# SCH_Esquematico_pastillero.net
KiCad netlist of a schematic drawn in EasyEDA
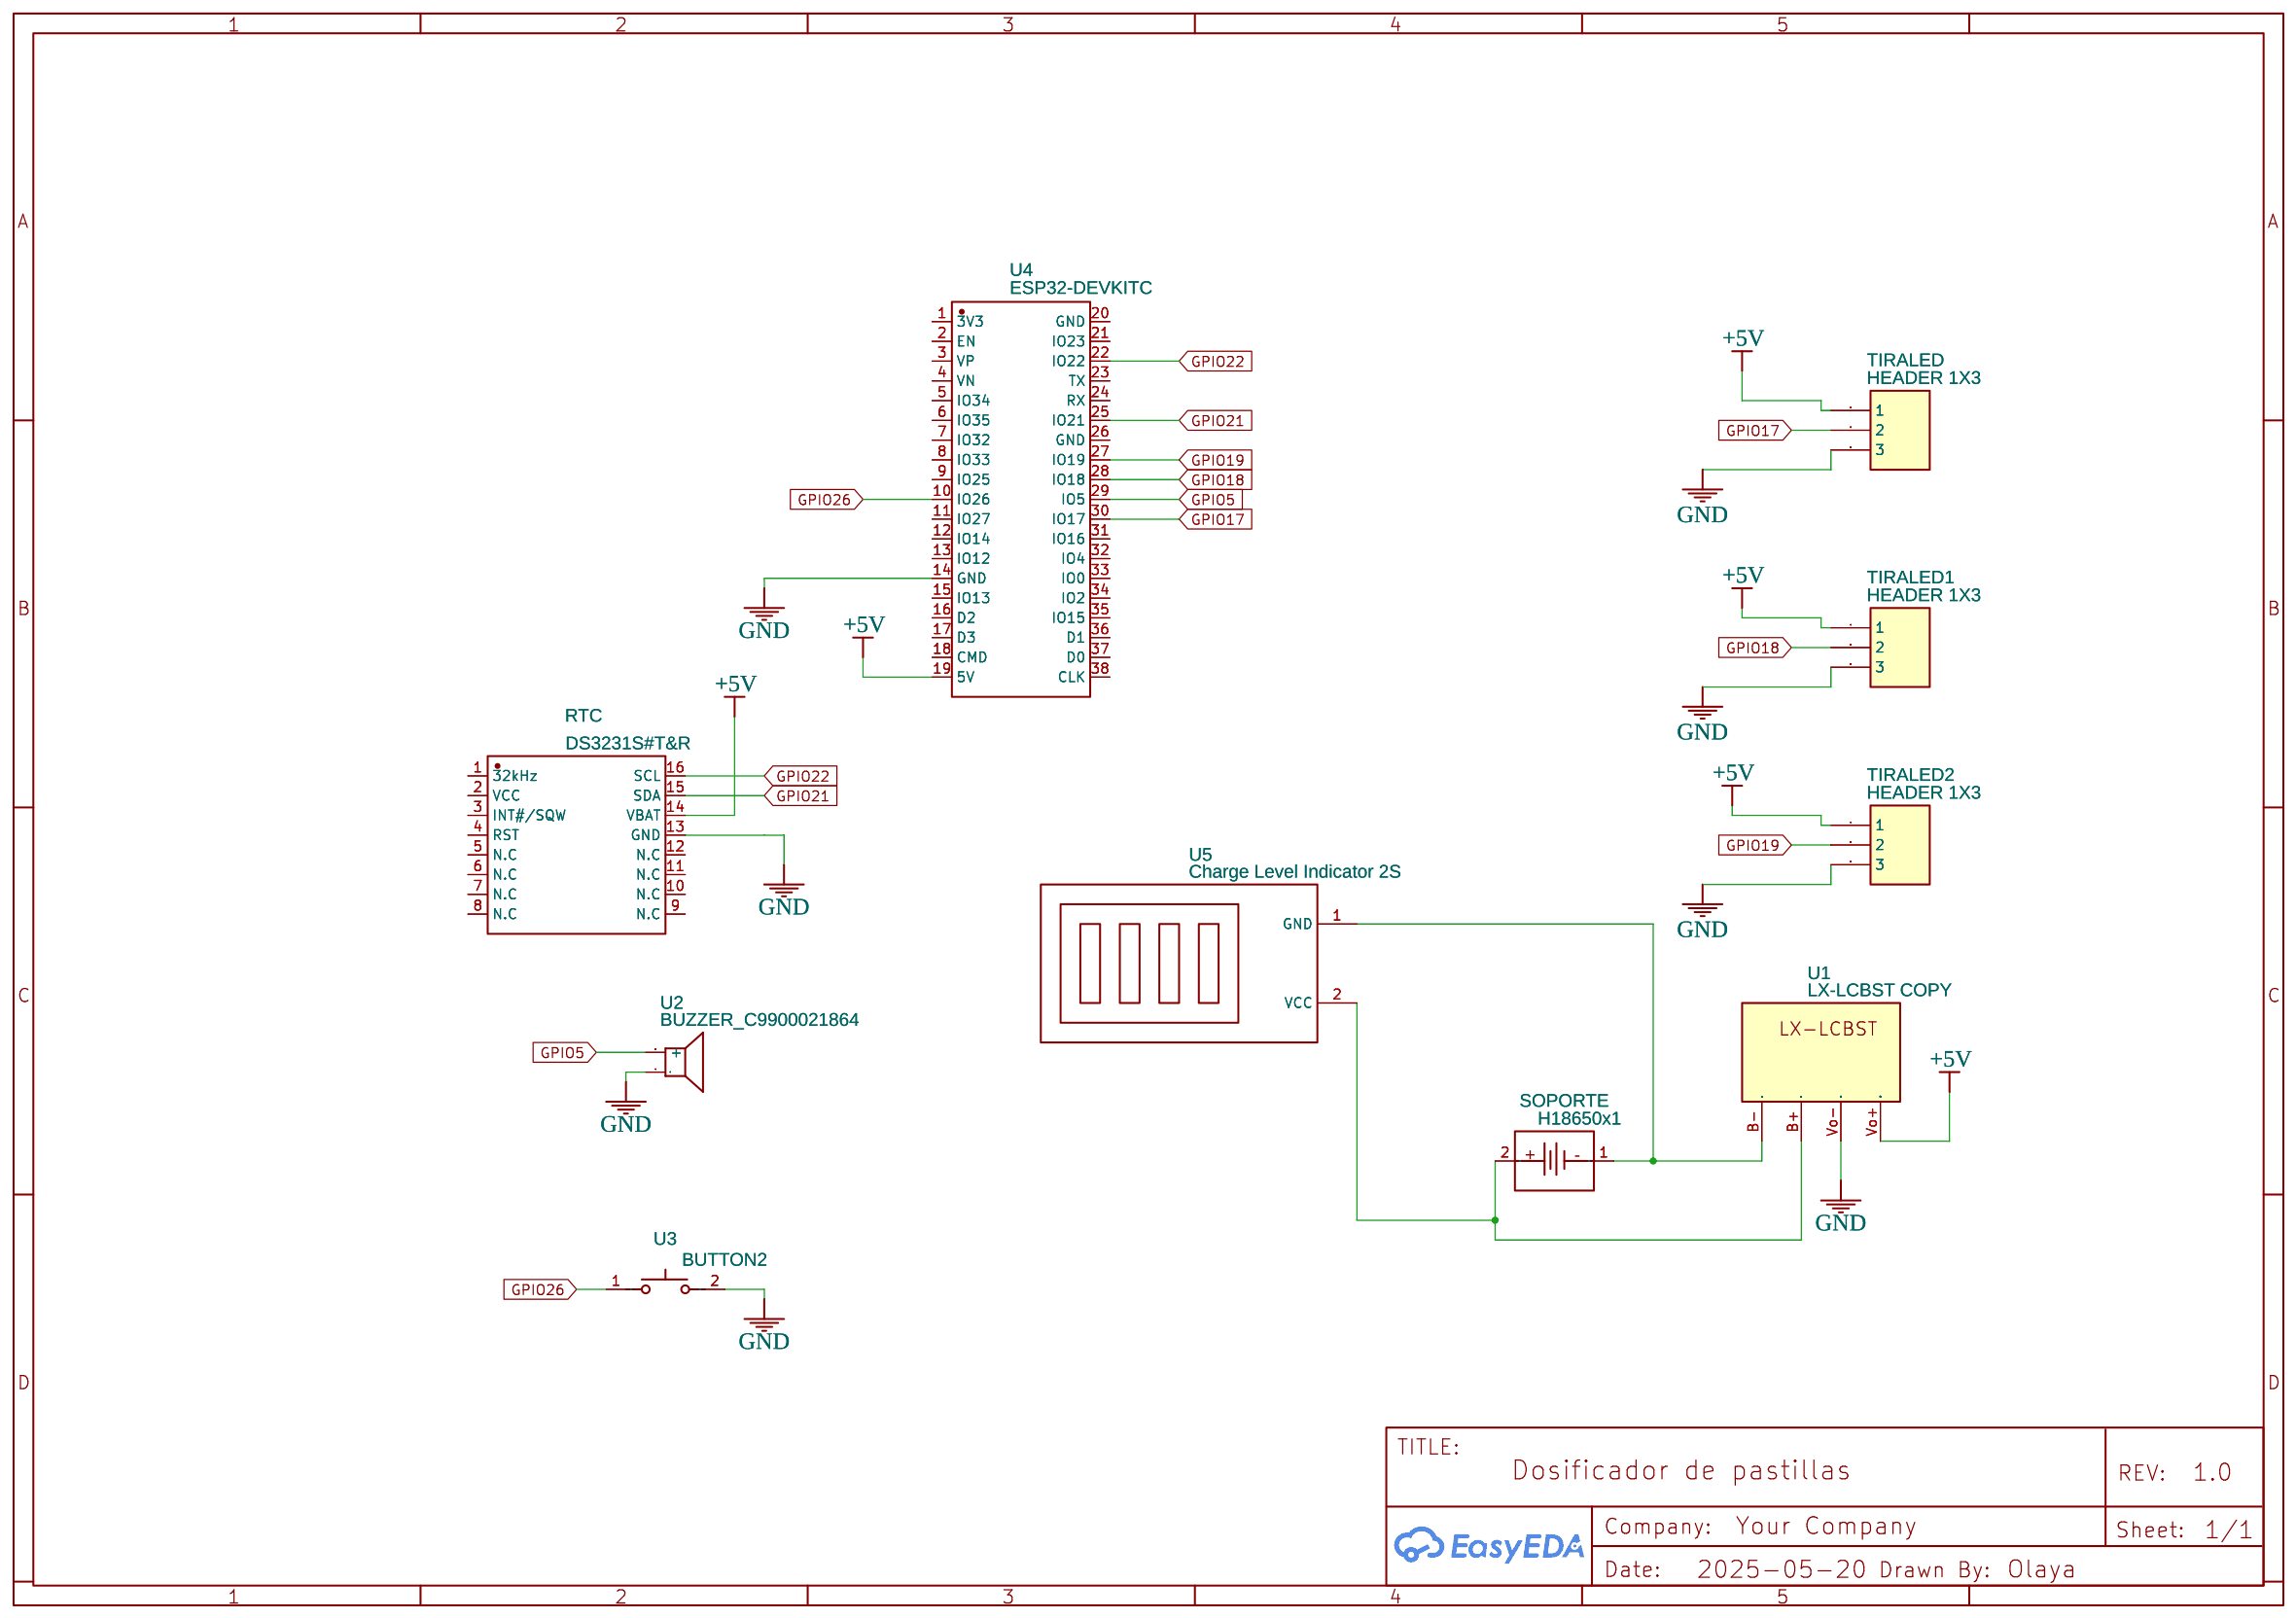
[diagram p0: schematic sheet]

(export (version "E")
  (design (tool "Eeschema 10.0.6"))
  (components
    (comp (ref "RTC")
      (value "DS3231S#T&R")
      (fields (field (name "Manufacturer") "ADI(亚德诺)/MAXIM(美信)"))
      (libsource (lib "") (part "DS3231S#T&amp;R"))
    )
    (comp (ref "SOPORTE") (value "H18650x1") (libsource (lib "") (part "H18650x1")))
    (comp (ref "TIRALED") (value "HEADER 1X3") (libsource (lib "") (part "HEADER 1X3")))
    (comp (ref "TIRALED1") (value "HEADER 1X3") (libsource (lib "") (part "HEADER 1X3")))
    (comp (ref "TIRALED2") (value "HEADER 1X3") (libsource (lib "") (part "HEADER 1X3")))
    (comp (ref "U1") (value "LX-LCBST COPY") (libsource (lib "") (part "LX-LCBST COPY")))
    (comp (ref "U2")
      (value "BUZZER_C9900021864")
      (fields (field (name "Manufacturer Part") "BUZZER"))
      (libsource (lib "") (part "BUZZER_C9900021864"))
    )
    (comp (ref "U3") (value "BUTTON2") (libsource (lib "") (part "BUTTON2")))
    (comp (ref "U4")
      (value "ESP32-DEVKITC")
      (fields
        (field (name "Manufacturer Part") "ESP32-DevKitC")
        (field (name "Manufacturer") "ESPRESSIF(乐鑫)")
      )
      (libsource (lib "") (part "ESP32-DEVKITC"))
    )
    (comp (ref "U5")
      (value "Charge Level Indicator 2S")
      (libsource (lib "") (part "Charge Level Indicator 2S"))
    )
  )
  (nets
    (net (code "1") (name "+5V") (class "Default")
      (node (ref "RTC") (pin "14") (pinfunction "VBAT_14") (pintype "unspecified"))
      (node (ref "TIRALED") (pin "1") (pinfunction "1_1") (pintype "unspecified"))
      (node (ref "TIRALED1") (pin "1") (pinfunction "1_1") (pintype "unspecified"))
      (node (ref "TIRALED2") (pin "1") (pinfunction "1_1") (pintype "unspecified"))
      (node (ref "U1") (pin "Vo+") (pinfunction "Vout+_Vo+") (pintype "unspecified"))
      (node (ref "U4") (pin "19") (pinfunction "5V_19") (pintype "unspecified"))
    )
    (net (code "2") (name "GND") (class "Default")
      (node (ref "RTC") (pin "13") (pinfunction "GND_13") (pintype "unspecified"))
      (node (ref "TIRALED") (pin "3") (pinfunction "3_3") (pintype "unspecified"))
      (node (ref "TIRALED1") (pin "3") (pinfunction "3_3") (pintype "unspecified"))
      (node (ref "TIRALED2") (pin "3") (pinfunction "3_3") (pintype "unspecified"))
      (node (ref "U1") (pin "Vo-") (pinfunction "Vout-_Vo-") (pintype "unspecified"))
      (node (ref "U2") (pin "1") (pinfunction "1_1") (pintype "unspecified"))
      (node (ref "U3") (pin "2") (pinfunction "2_2") (pintype "unspecified"))
      (node (ref "U4") (pin "14") (pinfunction "GND_14") (pintype "unspecified"))
    )
    (net (code "3") (name "GPIO5") (class "Default")
      (node (ref "U2") (pin "2") (pinfunction "+_2") (pintype "unspecified"))
      (node (ref "U4") (pin "29") (pinfunction "IO5_29") (pintype "unspecified"))
    )
    (net (code "4") (name "GPIO17") (class "Default")
      (node (ref "TIRALED") (pin "2") (pinfunction "2_2") (pintype "unspecified"))
      (node (ref "U4") (pin "30") (pinfunction "IO17_30") (pintype "unspecified"))
    )
    (net (code "5") (name "GPIO18") (class "Default")
      (node (ref "TIRALED1") (pin "2") (pinfunction "2_2") (pintype "unspecified"))
      (node (ref "U4") (pin "28") (pinfunction "IO18_28") (pintype "unspecified"))
    )
    (net (code "6") (name "GPIO19") (class "Default")
      (node (ref "TIRALED2") (pin "2") (pinfunction "2_2") (pintype "unspecified"))
      (node (ref "U4") (pin "27") (pinfunction "IO19_27") (pintype "unspecified"))
    )
    (net (code "7") (name "GPIO21") (class "Default")
      (node (ref "RTC") (pin "15") (pinfunction "SDA_15") (pintype "unspecified"))
      (node (ref "U4") (pin "25") (pinfunction "IO21_25") (pintype "unspecified"))
    )
    (net (code "8") (name "GPIO22") (class "Default")
      (node (ref "RTC") (pin "16") (pinfunction "SCL_16") (pintype "unspecified"))
      (node (ref "U4") (pin "22") (pinfunction "IO22_22") (pintype "unspecified"))
    )
    (net (code "9") (name "GPIO26") (class "Default")
      (node (ref "U3") (pin "1") (pinfunction "1_1") (pintype "unspecified"))
      (node (ref "U4") (pin "10") (pinfunction "IO26_10") (pintype "unspecified"))
    )
    (net (code "10") (name "Net-(U5-GND)") (class "Default")
      (node (ref "SOPORTE") (pin "1") (pinfunction "1_1") (pintype "input"))
      (node (ref "U1") (pin "B-") (pinfunction "B-_B-") (pintype "unspecified"))
      (node (ref "U5") (pin "1") (pinfunction "GND_1") (pintype "unspecified"))
    )
    (net (code "11") (name "Net-(U5-VCC)") (class "Default")
      (node (ref "SOPORTE") (pin "2") (pinfunction "2_2") (pintype "input"))
      (node (ref "U1") (pin "B+") (pinfunction "B+_B+") (pintype "unspecified"))
      (node (ref "U5") (pin "2") (pinfunction "VCC_2") (pintype "unspecified"))
    )
    (net (code "12") (name "unconnected-(RTC-32kHz-Pad1)") (class "Default")
      (node (ref "RTC") (pin "1") (pinfunction "32kHz_1") (pintype "unspecified"))
    )
    (net (code "13") (name "unconnected-(RTC-INT#{slash}SQW-Pad3)") (class "Default")
      (node (ref "RTC") (pin "3") (pinfunction "INT#/SQW_3") (pintype "unspecified"))
    )
    (net (code "14") (name "unconnected-(RTC-N.C-Pad5)") (class "Default")
      (node (ref "RTC") (pin "5") (pinfunction "N.C_5") (pintype "unspecified"))
    )
    (net (code "15") (name "unconnected-(RTC-N.C-Pad6)") (class "Default")
      (node (ref "RTC") (pin "6") (pinfunction "N.C_6") (pintype "unspecified"))
    )
    (net (code "16") (name "unconnected-(RTC-N.C-Pad7)") (class "Default")
      (node (ref "RTC") (pin "7") (pinfunction "N.C_7") (pintype "unspecified"))
    )
    (net (code "17") (name "unconnected-(RTC-N.C-Pad8)") (class "Default")
      (node (ref "RTC") (pin "8") (pinfunction "N.C_8") (pintype "unspecified"))
    )
    (net (code "18") (name "unconnected-(RTC-N.C-Pad9)") (class "Default")
      (node (ref "RTC") (pin "9") (pinfunction "N.C_9") (pintype "unspecified"))
    )
    (net (code "19") (name "unconnected-(RTC-N.C-Pad10)") (class "Default")
      (node (ref "RTC") (pin "10") (pinfunction "N.C_10") (pintype "unspecified"))
    )
    (net (code "20") (name "unconnected-(RTC-N.C-Pad11)") (class "Default")
      (node (ref "RTC") (pin "11") (pinfunction "N.C_11") (pintype "unspecified"))
    )
    (net (code "21") (name "unconnected-(RTC-N.C-Pad12)") (class "Default")
      (node (ref "RTC") (pin "12") (pinfunction "N.C_12") (pintype "unspecified"))
    )
    (net (code "22") (name "unconnected-(RTC-RST-Pad4)") (class "Default")
      (node (ref "RTC") (pin "4") (pinfunction "RST_4") (pintype "unspecified"))
    )
    (net (code "23") (name "unconnected-(RTC-VCC-Pad2)") (class "Default")
      (node (ref "RTC") (pin "2") (pinfunction "VCC_2") (pintype "unspecified"))
    )
    (net (code "24") (name "unconnected-(U4-3V3-Pad1)") (class "Default")
      (node (ref "U4") (pin "1") (pinfunction "3V3_1") (pintype "unspecified"))
    )
    (net (code "25") (name "unconnected-(U4-CLK-Pad38)") (class "Default")
      (node (ref "U4") (pin "38") (pinfunction "CLK_38") (pintype "unspecified"))
    )
    (net (code "26") (name "unconnected-(U4-CMD-Pad18)") (class "Default")
      (node (ref "U4") (pin "18") (pinfunction "CMD_18") (pintype "unspecified"))
    )
    (net (code "27") (name "unconnected-(U4-D0-Pad37)") (class "Default")
      (node (ref "U4") (pin "37") (pinfunction "D0_37") (pintype "unspecified"))
    )
    (net (code "28") (name "unconnected-(U4-D1-Pad36)") (class "Default")
      (node (ref "U4") (pin "36") (pinfunction "D1_36") (pintype "unspecified"))
    )
    (net (code "29") (name "unconnected-(U4-D2-Pad16)") (class "Default")
      (node (ref "U4") (pin "16") (pinfunction "D2_16") (pintype "unspecified"))
    )
    (net (code "30") (name "unconnected-(U4-D3-Pad17)") (class "Default")
      (node (ref "U4") (pin "17") (pinfunction "D3_17") (pintype "unspecified"))
    )
    (net (code "31") (name "unconnected-(U4-EN-Pad2)") (class "Default")
      (node (ref "U4") (pin "2") (pinfunction "EN_2") (pintype "unspecified"))
    )
    (net (code "32") (name "unconnected-(U4-GND-Pad20)") (class "Default")
      (node (ref "U4") (pin "20") (pinfunction "GND_20") (pintype "unspecified"))
    )
    (net (code "33") (name "unconnected-(U4-GND-Pad26)") (class "Default")
      (node (ref "U4") (pin "26") (pinfunction "GND_26") (pintype "unspecified"))
    )
    (net (code "34") (name "unconnected-(U4-IO0-Pad33)") (class "Default")
      (node (ref "U4") (pin "33") (pinfunction "IO0_33") (pintype "unspecified"))
    )
    (net (code "35") (name "unconnected-(U4-IO2-Pad34)") (class "Default")
      (node (ref "U4") (pin "34") (pinfunction "IO2_34") (pintype "unspecified"))
    )
    (net (code "36") (name "unconnected-(U4-IO4-Pad32)") (class "Default")
      (node (ref "U4") (pin "32") (pinfunction "IO4_32") (pintype "unspecified"))
    )
    (net (code "37") (name "unconnected-(U4-IO12-Pad13)") (class "Default")
      (node (ref "U4") (pin "13") (pinfunction "IO12_13") (pintype "unspecified"))
    )
    (net (code "38") (name "unconnected-(U4-IO13-Pad15)") (class "Default")
      (node (ref "U4") (pin "15") (pinfunction "IO13_15") (pintype "unspecified"))
    )
    (net (code "39") (name "unconnected-(U4-IO14-Pad12)") (class "Default")
      (node (ref "U4") (pin "12") (pinfunction "IO14_12") (pintype "unspecified"))
    )
    (net (code "40") (name "unconnected-(U4-IO15-Pad35)") (class "Default")
      (node (ref "U4") (pin "35") (pinfunction "IO15_35") (pintype "unspecified"))
    )
    (net (code "41") (name "unconnected-(U4-IO16-Pad31)") (class "Default")
      (node (ref "U4") (pin "31") (pinfunction "IO16_31") (pintype "unspecified"))
    )
    (net (code "42") (name "unconnected-(U4-IO23-Pad21)") (class "Default")
      (node (ref "U4") (pin "21") (pinfunction "IO23_21") (pintype "unspecified"))
    )
    (net (code "43") (name "unconnected-(U4-IO25-Pad9)") (class "Default")
      (node (ref "U4") (pin "9") (pinfunction "IO25_9") (pintype "unspecified"))
    )
    (net (code "44") (name "unconnected-(U4-IO27-Pad11)") (class "Default")
      (node (ref "U4") (pin "11") (pinfunction "IO27_11") (pintype "unspecified"))
    )
    (net (code "45") (name "unconnected-(U4-IO32-Pad7)") (class "Default")
      (node (ref "U4") (pin "7") (pinfunction "IO32_7") (pintype "unspecified"))
    )
    (net (code "46") (name "unconnected-(U4-IO33-Pad8)") (class "Default")
      (node (ref "U4") (pin "8") (pinfunction "IO33_8") (pintype "unspecified"))
    )
    (net (code "47") (name "unconnected-(U4-IO34-Pad5)") (class "Default")
      (node (ref "U4") (pin "5") (pinfunction "IO34_5") (pintype "unspecified"))
    )
    (net (code "48") (name "unconnected-(U4-IO35-Pad6)") (class "Default")
      (node (ref "U4") (pin "6") (pinfunction "IO35_6") (pintype "unspecified"))
    )
    (net (code "49") (name "unconnected-(U4-RX-Pad24)") (class "Default")
      (node (ref "U4") (pin "24") (pinfunction "RX_24") (pintype "unspecified"))
    )
    (net (code "50") (name "unconnected-(U4-TX-Pad23)") (class "Default")
      (node (ref "U4") (pin "23") (pinfunction "TX_23") (pintype "unspecified"))
    )
    (net (code "51") (name "unconnected-(U4-VN-Pad4)") (class "Default")
      (node (ref "U4") (pin "4") (pinfunction "VN_4") (pintype "unspecified"))
    )
    (net (code "52") (name "unconnected-(U4-VP-Pad3)") (class "Default")
      (node (ref "U4") (pin "3") (pinfunction "VP_3") (pintype "unspecified"))
    )
  )
)
